# 03_Power_Buck_24V_3_3V.net
KiCad netlist of a schematic drawn in Altium Designer
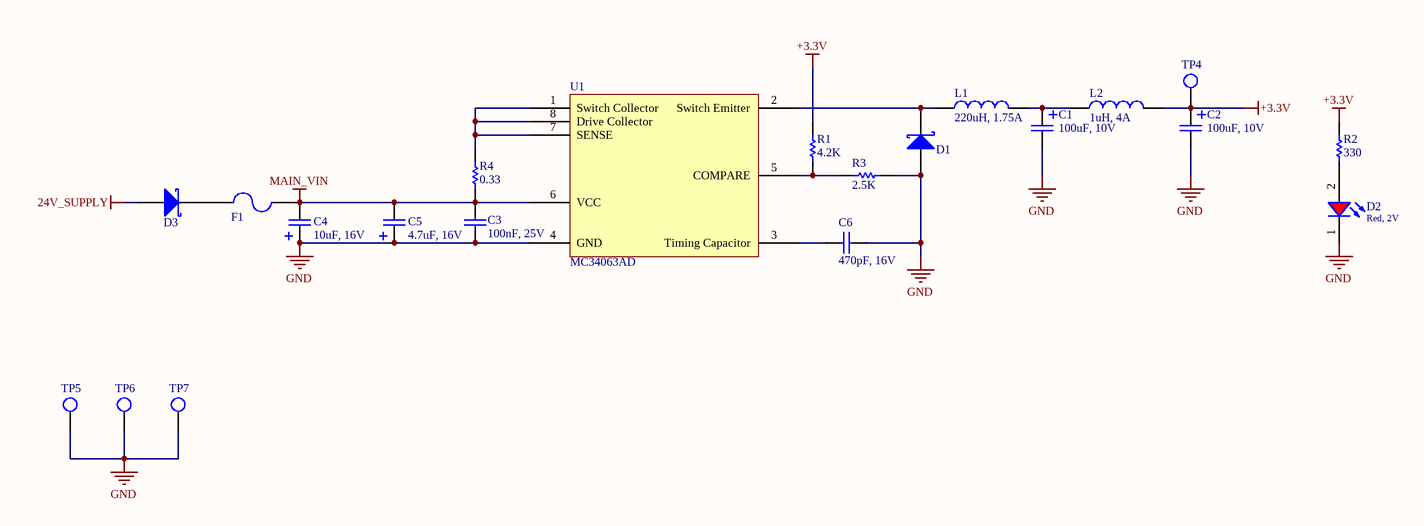
[diagram p0: 03_Power_Buck_24V_3.3V.SchDoc]

(export (version "E")
  (design (tool "Eeschema 10.0.6"))
  (components
    (comp (ref "C1")
      (value "100uF, 10V")
      (footprint "TAN1210")
      (fields (field (name "Comment") "Tantalum Capacitor"))
      (libsource (lib "MiclsLib") (part "Tantalum Capacitor"))
    )
    (comp (ref "C2")
      (value "100uF, 10V")
      (footprint "TAN1210")
      (fields (field (name "Comment") "Tantalum Capacitor"))
      (libsource (lib "MiclsLib") (part "Tantalum Capacitor"))
    )
    (comp (ref "C3")
      (value "100nF, 25V")
      (footprint "WCAP-CSGP_0603_H=0.8mm_Reflow")
      (description "WCAP-CSGP Multilayer Ceramic Chip Capacitor, General Purpose, size 0603, X7R, 100nF, 25V")
      (fields
        (field (name "MANUFACTURER PART NUMBER") "885012206071")
        (field (name "MANUFACTURER") "Wurth Elektronik")
      )
      (libsource (lib "Altium_WCAP-CSGP (rev20a)") (part "885012206071"))
    )
    (comp (ref "C4")
      (value "10uF, 16V")
      (footprint "TAN1206")
      (fields (field (name "Comment") "Tantalum Capacitor"))
      (libsource (lib "MiclsLib") (part "Tantalum Capacitor"))
    )
    (comp (ref "C5")
      (value "4.7uF, 16V")
      (footprint "TAN1206")
      (fields (field (name "Comment") "Tantalum Capacitor"))
      (libsource (lib "MiclsLib") (part "Tantalum Capacitor"))
    )
    (comp (ref "C6")
      (value "470pF, 16V")
      (footprint "WCAP-CSGP_0603_H=0.8mm_Reflow")
      (description "WCAP-CSGP Multilayer Ceramic Chip Capacitor, General Purpose, size 0603, NP0, 470pF, 16V")
      (fields
        (field (name "MANUFACTURER PART NUMBER") "885012006027")
        (field (name "MANUFACTURER") "Wurth Elektronik")
      )
      (libsource (lib "Altium_WCAP-CSGP (rev20a)") (part "885012006027"))
    )
    (comp (ref "D1")
      (value "D Schottky")
      (footprint "SS34")
      (description "Schottky Diode")
      (fields (field (name "PUBLISHER") "Altium Limited"))
      (libsource (lib "PIF_Library") (part "D Schottky"))
    )
    (comp (ref "D2")
      (value "Red, 2V")
      (footprint "WL-SMCW_0603_H=0.7mm")
      (description "WL-SMCW SMT Mono-color Chip LED Waterclear, size 0603, Red, 2V, 140deg")
      (fields (field (name "PART NUMBER") "150060RS75000") (field (name "PUBLISHER") "Wurth Elektronik"))
      (libsource (lib "Altium_WL-SMCW (rev20a)") (part "150060RS75000"))
    )
    (comp (ref "D3")
      (value "D Schottky")
      (footprint "SS34")
      (description "Schottky Diode")
      (fields (field (name "PUBLISHER") "Altium Limited"))
      (libsource (lib "PIF_Library") (part "D Schottky"))
    )
    (comp (ref "F1") (value "Fuse") (footprint "FUSE SMD") (libsource (lib "PIF_Library") (part "Fuse")))
    (comp (ref "L1")
      (value "220uH, 1.75A")
      (footprint "WE-PD2A_5848")
      (description "WE-PD2A SMT Power Inductor, size 5848, 220uH, 0.41A")
      (fields
        (field (name "MANUFACTURER PART NUMBER") "784774222")
        (field (name "MANUFACTURER") "Wurth Elektronik")
      )
      (libsource (lib "Altium_WE-PD2A (rev20a)") (part "784774222"))
    )
    (comp (ref "L2")
      (value "1uH, 4A")
      (footprint "WE-PD2A_4532")
      (description "WE-PD2A SMT Power Inductor, size 4532, 1uH, 4A")
      (fields
        (field (name "MANUFACTURER PART NUMBER") "7847730")
        (field (name "MANUFACTURER") "Wurth Elektronik")
      )
      (libsource (lib "Altium_WE-PD2A (rev20a)") (part "7847730"))
    )
    (comp (ref "R1")
      (value "4.2K")
      (footprint "RES-SM-0603")
      (description "Resistor")
      (fields (field (name "Comment") "RESISTOR SMD"))
      (libsource (lib "PIF_Library") (part "RESISTOR SMD"))
    )
    (comp (ref "R2")
      (value "330")
      (footprint "RES-SM-0603")
      (description "Resistor")
      (fields (field (name "Comment") "RESISTOR SMD"))
      (libsource (lib "PIF_Library") (part "RESISTOR SMD"))
    )
    (comp (ref "R3")
      (value "2.5K")
      (footprint "RES-SM-0603")
      (description "Resistor")
      (fields (field (name "Comment") "RESISTOR SMD"))
      (libsource (lib "PIF_Library") (part "RESISTOR SMD"))
    )
    (comp (ref "R4")
      (value "0.33")
      (footprint "RES-SM-0805")
      (description "Resistor")
      (fields (field (name "Comment") "RESISTOR SMD"))
      (libsource (lib "PIF_Library") (part "RESISTOR SMD"))
    )
    (comp (ref "TP4") (value "Test point") (footprint "TP") (libsource (lib "MiclsLib") (part "TP")))
    (comp (ref "TP5") (value "Test point") (footprint "TP") (libsource (lib "MiclsLib") (part "TP")))
    (comp (ref "TP6") (value "Test point") (footprint "TP") (libsource (lib "MiclsLib") (part "TP")))
    (comp (ref "TP7") (value "Test point") (footprint "TP") (libsource (lib "MiclsLib") (part "TP")))
    (comp (ref "U1")
      (value "MC34063AD")
      (footprint "SOIC127P600X170-8N")
      (description "1.5-A boost, buck, inverting switching regulator, operation from 0°C to 70°C")
      (fields (field (name "MANUFACTURER") "Texas Instruments"))
      (libsource (lib "PowerSupply") (part "MC34063"))
    )
  )
  (nets
    (net (code "1") (name "+3.3V") (class "Default")
      (node (ref "C2") (pin "1") (pinfunction "1_1") (pintype "passive"))
      (node (ref "L2") (pin "2") (pinfunction "2_2") (pintype "passive"))
      (node (ref "R1") (pin "2") (pinfunction "2_2") (pintype "passive"))
      (node (ref "R2") (pin "2") (pinfunction "2_2") (pintype "passive"))
      (node (ref "TP4") (pin "1") (pinfunction "27_1") (pintype "passive"))
    )
    (net (code "2") (name "24V_SUPPLY") (class "Default")
      (node (ref "D3") (pin "1") (pinfunction "A_1") (pintype "passive"))
    )
    (net (code "3") (name "GND") (class "Default")
      (node (ref "C1") (pin "2") (pinfunction "2_2") (pintype "passive"))
      (node (ref "C2") (pin "2") (pinfunction "2_2") (pintype "passive"))
      (node (ref "C3") (pin "1") (pinfunction "1_1") (pintype "passive"))
      (node (ref "C4") (pin "1") (pinfunction "1_1") (pintype "passive"))
      (node (ref "C5") (pin "1") (pinfunction "1_1") (pintype "passive"))
      (node (ref "C6") (pin "2") (pinfunction "2_2") (pintype "passive"))
      (node (ref "D1") (pin "1") (pinfunction "A_1") (pintype "passive"))
      (node (ref "D2") (pin "1") (pinfunction "K_1") (pintype "passive"))
      (node (ref "R3") (pin "1") (pinfunction "1_1") (pintype "passive"))
      (node (ref "TP5") (pin "1") (pinfunction "27_1") (pintype "passive"))
      (node (ref "TP6") (pin "1") (pinfunction "27_1") (pintype "passive"))
      (node (ref "TP7") (pin "1") (pinfunction "27_1") (pintype "passive"))
      (node (ref "U1") (pin "4") (pinfunction "GND_4") (pintype "passive"))
    )
    (net (code "4") (name "MAIN_VIN") (class "Default")
      (node (ref "C3") (pin "2") (pinfunction "2_2") (pintype "passive"))
      (node (ref "C4") (pin "2") (pinfunction "2_2") (pintype "passive"))
      (node (ref "C5") (pin "2") (pinfunction "2_2") (pintype "passive"))
      (node (ref "F1") (pin "2") (pinfunction "2_2") (pintype "passive"))
      (node (ref "R4") (pin "1") (pinfunction "1_1") (pintype "passive"))
      (node (ref "U1") (pin "6") (pinfunction "VCC_6") (pintype "passive"))
    )
    (net (code "5") (name "Net-(C1-Pad1)") (class "Default")
      (node (ref "C1") (pin "1") (pinfunction "1_1") (pintype "passive"))
      (node (ref "L1") (pin "2") (pinfunction "2_2") (pintype "passive"))
      (node (ref "L2") (pin "1") (pinfunction "1_1") (pintype "passive"))
    )
    (net (code "6") (name "Net-(D1-K)") (class "Default")
      (node (ref "D1") (pin "2") (pinfunction "K_2") (pintype "passive"))
      (node (ref "L1") (pin "1") (pinfunction "1_1") (pintype "passive"))
      (node (ref "U1") (pin "2") (pinfunction "Switch_Emitter_2") (pintype "passive"))
    )
    (net (code "7") (name "Net-(D2-A)") (class "Default")
      (node (ref "D2") (pin "2") (pinfunction "A_2") (pintype "passive"))
      (node (ref "R2") (pin "1") (pinfunction "1_1") (pintype "passive"))
    )
    (net (code "8") (name "Net-(D3-K)") (class "Default")
      (node (ref "D3") (pin "2") (pinfunction "K_2") (pintype "passive"))
      (node (ref "F1") (pin "1") (pinfunction "1_1") (pintype "passive"))
    )
    (net (code "9") (name "Net-(U1-COMPARE)") (class "Default")
      (node (ref "R1") (pin "1") (pinfunction "1_1") (pintype "passive"))
      (node (ref "R3") (pin "2") (pinfunction "2_2") (pintype "passive"))
      (node (ref "U1") (pin "5") (pinfunction "COMPARE_5") (pintype "passive"))
    )
    (net (code "10") (name "Net-(U1-Drive_Collector)") (class "Default")
      (node (ref "R4") (pin "2") (pinfunction "2_2") (pintype "passive"))
      (node (ref "U1") (pin "1") (pinfunction "Switch_Collector_1") (pintype "passive"))
      (node (ref "U1") (pin "7") (pinfunction "SENSE_7") (pintype "passive"))
      (node (ref "U1") (pin "8") (pinfunction "Drive_Collector_8") (pintype "passive"))
    )
    (net (code "11") (name "Net-(U1-Timing_Capacitor)") (class "Default")
      (node (ref "C6") (pin "1") (pinfunction "1_1") (pintype "passive"))
      (node (ref "U1") (pin "3") (pinfunction "Timing_Capacitor_3") (pintype "passive"))
    )
  )
)
